# Ethernet_Connector.net
KiCad netlist of a schematic drawn in Altium Designer
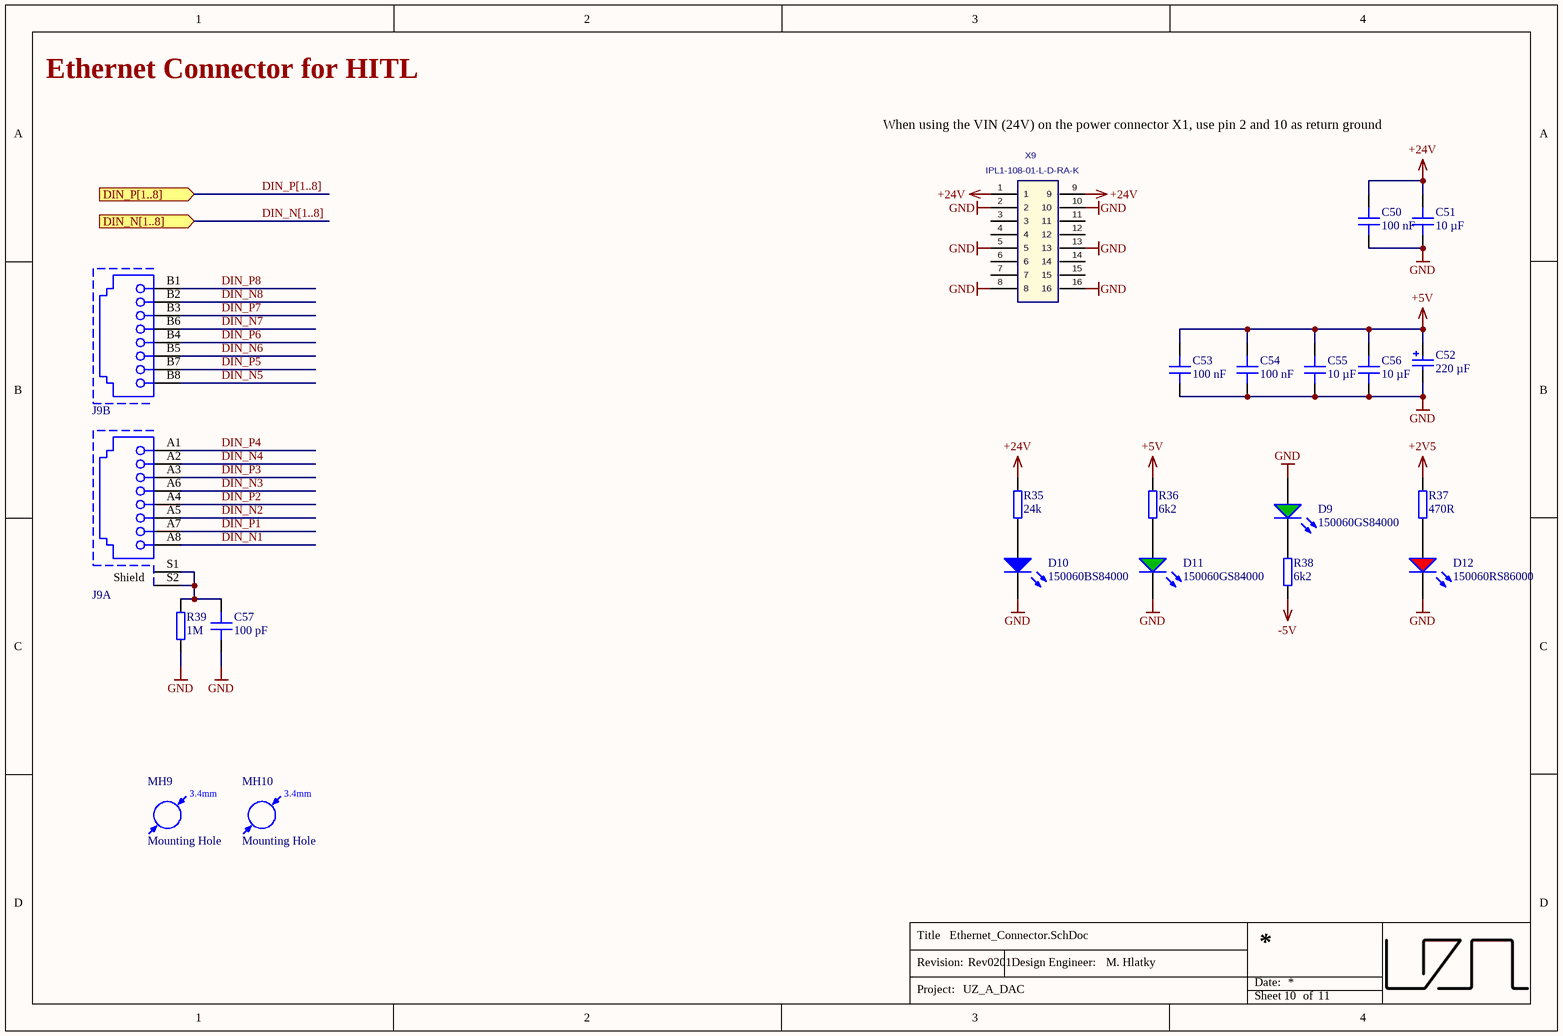
[diagram p0: Ethernet_Connector.SchDoc]

(export (version "E")
  (design (tool "Eeschema 10.0.6"))
  (components
    (comp (ref "C50")
      (value "100 nF")
      (footprint "C_0603")
      (description "Capacitor 0603, 6.3 VDC, 100 nF, X5R")
      (fields
        (field (name "MANUFACTURER PART NUMBER") "C0603C104K9PACTU")
        (field (name "MANUFACTURER") "KEMET")
        (field (name "CREATED FROM") "MGremer")
      )
      (libsource (lib "user") (part "Capacitor"))
    )
    (comp (ref "C51")
      (value "10 µF")
      (footprint "C_1206")
      (description "Capacitor 1206, 50 VDC, 10 µF, X5R")
      (fields
        (field (name "MANUFACTURER PART NUMBER") "GRT31CR61H106KE01L")
        (field (name "MANUFACTURER") "Murata Electronics")
        (field (name "CREATED FROM") "MGremer")
      )
      (libsource (lib "user") (part "Capacitor"))
    )
    (comp (ref "C52")
      (value "220 µF")
      (footprint "WCAP-PSHP_D8mm x L7.7mm")
      (description "Capacitor WCAP, 16 VDC, 220 µF")
      (fields
        (field (name "MANUFACTURER PART NUMBER") "875115350002")
        (field (name "MANUFACTURER") "Wuerth Elektronik")
        (field (name "CREATED FROM") "MGremer")
      )
      (libsource (lib "user") (part "Capacitor_Polarized"))
    )
    (comp (ref "C53")
      (value "100 nF")
      (footprint "C_0603")
      (description "Capacitor 0603, 6.3 VDC, 100 nF, X5R")
      (fields
        (field (name "MANUFACTURER PART NUMBER") "C0603C104K9PACTU")
        (field (name "MANUFACTURER") "KEMET")
        (field (name "CREATED FROM") "MGremer")
      )
      (libsource (lib "user") (part "Capacitor"))
    )
    (comp (ref "C54")
      (value "100 nF")
      (footprint "C_0603")
      (description "Capacitor 0603, 6.3 VDC, 100 nF, X5R")
      (fields
        (field (name "MANUFACTURER PART NUMBER") "C0603C104K9PACTU")
        (field (name "MANUFACTURER") "KEMET")
        (field (name "CREATED FROM") "MGremer")
      )
      (libsource (lib "user") (part "Capacitor"))
    )
    (comp (ref "C55")
      (value "10 µF")
      (footprint "C_1206")
      (description "Capacitor 1206, 50 VDC, 10 µF, X5R")
      (fields
        (field (name "MANUFACTURER PART NUMBER") "GRT31CR61H106KE01L")
        (field (name "MANUFACTURER") "Murata Electronics")
        (field (name "CREATED FROM") "MGremer")
      )
      (libsource (lib "user") (part "Capacitor"))
    )
    (comp (ref "C56")
      (value "10 µF")
      (footprint "C_1206")
      (description "Capacitor 1206, 50 VDC, 10 µF, X5R")
      (fields
        (field (name "MANUFACTURER PART NUMBER") "GRT31CR61H106KE01L")
        (field (name "MANUFACTURER") "Murata Electronics")
        (field (name "CREATED FROM") "MGremer")
      )
      (libsource (lib "user") (part "Capacitor"))
    )
    (comp (ref "C57")
      (value "100 pF")
      (footprint "C_1206")
      (description "Capacitor 1206, 1 kVDC, 100 pF, C0G")
      (fields
        (field (name "MANUFACTURER PART NUMBER") "885342008009")
        (field (name "MANUFACTURER") "Wuerth Elektronik")
        (field (name "CREATED FROM") "MGremer")
      )
      (libsource (lib "user") (part "Capacitor"))
    )
    (comp (ref "D9")
      (value "150060GS84000")
      (footprint "WL-SMCW_0603")
      (description "WL-SMCW SMD Mono-color Chip LED Waterclear Green")
      (fields (field (name "MANUFACTURER") "Wuerth Elektronik") (field (name "CREATED FROM") "MGremer"))
      (libsource (lib "user") (part "LED_Green"))
    )
    (comp (ref "D10")
      (value "150060BS84000")
      (footprint "WL-SMCW_0603")
      (description "WL-SMCW SMD Mono-color Chip LED Waterclear Blue")
      (fields (field (name "MANUFACTURER") "Wuerth Elektronik") (field (name "CREATED FROM") "MGremer"))
      (libsource (lib "user") (part "LED_Blue"))
    )
    (comp (ref "D11")
      (value "150060GS84000")
      (footprint "WL-SMCW_0603")
      (description "WL-SMCW SMD Mono-color Chip LED Waterclear Green")
      (fields (field (name "MANUFACTURER") "Wuerth Elektronik") (field (name "CREATED FROM") "MGremer"))
      (libsource (lib "user") (part "LED_Green"))
    )
    (comp (ref "D12")
      (value "150060RS86000")
      (footprint "WL-SMCW_0603")
      (description "WL-SMCW SMD Mono-color Chip LED Waterclear Red")
      (fields (field (name "MANUFACTURER") "Wuerth Elektronik") (field (name "CREATED FROM") "MGremer"))
      (libsource (lib "user") (part "LED_Red"))
    )
    (comp (ref "J9")
      (value "RJHSE-5380-02")
      (footprint "RJHSE-5380-02")
      (description "TAB-UP, MULTIPORT, RIGHT ANGLE OR VERTICAL WITH SHIELD AND INTEGRATED LEDs")
      (fields (field (name "MF") "Amphenol") (field (name "CREATED FROM") "MHlatky"))
      (libsource (lib "user") (part "RJHSE-5380-02"))
    )
    (comp (ref "MH9")
      (value "Mounting Hole")
      (footprint "MH_3.4")
      (fields (field (name "CREATED FROM") "MHlatky"))
      (libsource (lib "user") (part "Mounting Hole"))
    )
    (comp (ref "MH10")
      (value "Mounting Hole")
      (footprint "MH_3.4")
      (fields (field (name "CREATED FROM") "MHlatky"))
      (libsource (lib "user") (part "Mounting Hole"))
    )
    (comp (ref "R35")
      (value "24k")
      (footprint "RES 0603_1608")
      (description "SMD resistor E24 series")
      (fields
        (field (name "MANUFACTURER PART NUMBER") "RK73B1JTTD243J")
        (field (name "MANUFACTURER") "KOA Speer")
        (field (name "CREATED FROM") "MGremer")
      )
      (libsource (lib "user") (part "Resistor"))
    )
    (comp (ref "R36")
      (value "6k2")
      (footprint "RES 0603_1608")
      (description "SMD resistor E24 series")
      (fields
        (field (name "MANUFACTURER PART NUMBER") "RK73B1JTTD622J")
        (field (name "MANUFACTURER") "KOA Speer")
        (field (name "CREATED FROM") "MGremer")
      )
      (libsource (lib "user") (part "Resistor"))
    )
    (comp (ref "R37")
      (value "470R")
      (footprint "RES 0603_1608")
      (description "SMD resistor E24 series")
      (fields
        (field (name "MANUFACTURER PART NUMBER") "RK73B1JTTD471J")
        (field (name "MANUFACTURER") "KOA Speer")
        (field (name "CREATED FROM") "MGremer")
      )
      (libsource (lib "user") (part "Resistor"))
    )
    (comp (ref "R38")
      (value "6k2")
      (footprint "RES 0603_1608")
      (description "SMD resistor E24 series")
      (fields
        (field (name "MANUFACTURER PART NUMBER") "RK73B1JTTD622J")
        (field (name "MANUFACTURER") "KOA Speer")
        (field (name "CREATED FROM") "MGremer")
      )
      (libsource (lib "user") (part "Resistor"))
    )
    (comp (ref "R39")
      (value "1M")
      (footprint "RES 0603_1608")
      (description "SMD resistor 1%")
      (fields
        (field (name "MANUFACTURER PART NUMBER") "CRCW06031M00FKEAC")
        (field (name "MANUFACTURER") "Vishay / Dale")
        (field (name "CREATED FROM") "MGremer")
      )
      (libsource (lib "user") (part "Resistor"))
    )
    (comp (ref "X9")
      (value "IPL1-108-01-L-D-RA-K")
      (footprint "IPL1-108-01-L-D-RA-K")
      (description "2.54 mm Double Row Termin Assembly (right angle)")
      (fields (field (name "MANUFACTURER") "SAMTEC") (field (name "CREATED FROM") "MGremer"))
      (libsource (lib "user") (part "IPL1-108-XX-X-D-X"))
    )
  )
  (nets
    (net (code "1") (name "+2V5") (class "Default")
      (node (ref "R37") (pin "2") (pinfunction "2_2") (pintype "passive"))
    )
    (net (code "2") (name "+5V") (class "Default")
      (node (ref "C52") (pin "1") (pinfunction "P_1") (pintype "passive"))
      (node (ref "C53") (pin "2") (pinfunction "2_2") (pintype "passive"))
      (node (ref "C54") (pin "2") (pinfunction "2_2") (pintype "passive"))
      (node (ref "C55") (pin "2") (pinfunction "2_2") (pintype "passive"))
      (node (ref "C56") (pin "2") (pinfunction "2_2") (pintype "passive"))
      (node (ref "R36") (pin "2") (pinfunction "2_2") (pintype "passive"))
    )
    (net (code "3") (name "+24V") (class "Default")
      (node (ref "C50") (pin "2") (pinfunction "2_2") (pintype "passive"))
      (node (ref "C51") (pin "2") (pinfunction "2_2") (pintype "passive"))
      (node (ref "R35") (pin "2") (pinfunction "2_2") (pintype "passive"))
      (node (ref "X9") (pin "1") (pinfunction "1_1") (pintype "passive"))
      (node (ref "X9") (pin "9") (pinfunction "9_9") (pintype "passive"))
    )
    (net (code "4") (name "-5V") (class "Default")
      (node (ref "R38") (pin "1") (pinfunction "1_1") (pintype "passive"))
    )
    (net (code "5") (name "/DIN_N1") (class "Default")
      (node (ref "J9") (pin "A8") (pinfunction "A8_A8") (pintype "passive"))
    )
    (net (code "6") (name "/DIN_N2") (class "Default")
      (node (ref "J9") (pin "A5") (pinfunction "A5_A5") (pintype "passive"))
    )
    (net (code "7") (name "/DIN_N3") (class "Default")
      (node (ref "J9") (pin "A6") (pinfunction "A6_A6") (pintype "passive"))
    )
    (net (code "8") (name "/DIN_N4") (class "Default")
      (node (ref "J9") (pin "A2") (pinfunction "A2_A2") (pintype "passive"))
    )
    (net (code "9") (name "/DIN_N5") (class "Default")
      (node (ref "J9") (pin "B8") (pinfunction "B8_B8") (pintype "passive"))
    )
    (net (code "10") (name "/DIN_N6") (class "Default")
      (node (ref "J9") (pin "B5") (pinfunction "B5_B5") (pintype "passive"))
    )
    (net (code "11") (name "/DIN_N7") (class "Default")
      (node (ref "J9") (pin "B6") (pinfunction "B6_B6") (pintype "passive"))
    )
    (net (code "12") (name "/DIN_N8") (class "Default")
      (node (ref "J9") (pin "B2") (pinfunction "B2_B2") (pintype "passive"))
    )
    (net (code "14") (name "/DIN_P1") (class "Default")
      (node (ref "J9") (pin "A7") (pinfunction "A7_A7") (pintype "passive"))
    )
    (net (code "15") (name "/DIN_P2") (class "Default")
      (node (ref "J9") (pin "A4") (pinfunction "A4_A4") (pintype "passive"))
    )
    (net (code "16") (name "/DIN_P3") (class "Default")
      (node (ref "J9") (pin "A3") (pinfunction "A3_A3") (pintype "passive"))
    )
    (net (code "17") (name "/DIN_P4") (class "Default")
      (node (ref "J9") (pin "A1") (pinfunction "A1_A1") (pintype "passive"))
    )
    (net (code "18") (name "/DIN_P5") (class "Default")
      (node (ref "J9") (pin "B7") (pinfunction "B7_B7") (pintype "passive"))
    )
    (net (code "19") (name "/DIN_P6") (class "Default")
      (node (ref "J9") (pin "B4") (pinfunction "B4_B4") (pintype "passive"))
    )
    (net (code "20") (name "/DIN_P7") (class "Default")
      (node (ref "J9") (pin "B3") (pinfunction "B3_B3") (pintype "passive"))
    )
    (net (code "21") (name "/DIN_P8") (class "Default")
      (node (ref "J9") (pin "B1") (pinfunction "B1_B1") (pintype "passive"))
    )
    (net (code "23") (name "GND") (class "Default")
      (node (ref "C50") (pin "1") (pinfunction "1_1") (pintype "passive"))
      (node (ref "C51") (pin "1") (pinfunction "1_1") (pintype "passive"))
      (node (ref "C52") (pin "2") (pinfunction "N_2") (pintype "passive"))
      (node (ref "C53") (pin "1") (pinfunction "1_1") (pintype "passive"))
      (node (ref "C54") (pin "1") (pinfunction "1_1") (pintype "passive"))
      (node (ref "C55") (pin "1") (pinfunction "1_1") (pintype "passive"))
      (node (ref "C56") (pin "1") (pinfunction "1_1") (pintype "passive"))
      (node (ref "C57") (pin "1") (pinfunction "1_1") (pintype "passive"))
      (node (ref "D10") (pin "1") (pinfunction "K_1") (pintype "passive"))
      (node (ref "D11") (pin "1") (pinfunction "K_1") (pintype "passive"))
      (node (ref "D12") (pin "1") (pinfunction "K_1") (pintype "passive"))
      (node (ref "D9") (pin "2") (pinfunction "A_2") (pintype "passive"))
      (node (ref "R39") (pin "1") (pinfunction "1_1") (pintype "passive"))
      (node (ref "X9") (pin "10") (pinfunction "10_10") (pintype "passive"))
      (node (ref "X9") (pin "13") (pinfunction "13_13") (pintype "passive"))
      (node (ref "X9") (pin "16") (pinfunction "16_16") (pintype "passive"))
      (node (ref "X9") (pin "2") (pinfunction "2_2") (pintype "passive"))
      (node (ref "X9") (pin "5") (pinfunction "5_5") (pintype "passive"))
      (node (ref "X9") (pin "8") (pinfunction "8_8") (pintype "passive"))
    )
    (net (code "24") (name "Net-(C57-Pad2)") (class "Default")
      (node (ref "C57") (pin "2") (pinfunction "2_2") (pintype "passive"))
      (node (ref "J9") (pin "S1") (pinfunction "S1_S1") (pintype "passive"))
      (node (ref "J9") (pin "S2") (pinfunction "S2_S2") (pintype "passive"))
      (node (ref "R39") (pin "2") (pinfunction "2_2") (pintype "passive"))
    )
    (net (code "25") (name "Net-(D9-K)") (class "Default")
      (node (ref "D9") (pin "1") (pinfunction "K_1") (pintype "passive"))
      (node (ref "R38") (pin "2") (pinfunction "2_2") (pintype "passive"))
    )
    (net (code "26") (name "Net-(D10-A)") (class "Default")
      (node (ref "D10") (pin "2") (pinfunction "A_2") (pintype "passive"))
      (node (ref "R35") (pin "1") (pinfunction "1_1") (pintype "passive"))
    )
    (net (code "27") (name "Net-(D11-A)") (class "Default")
      (node (ref "D11") (pin "2") (pinfunction "A_2") (pintype "passive"))
      (node (ref "R36") (pin "1") (pinfunction "1_1") (pintype "passive"))
    )
    (net (code "28") (name "Net-(D12-A)") (class "Default")
      (node (ref "D12") (pin "2") (pinfunction "A_2") (pintype "passive"))
      (node (ref "R37") (pin "1") (pinfunction "1_1") (pintype "passive"))
    )
    (net (code "29") (name "unconnected-(X9-Pad3)") (class "Default")
      (node (ref "X9") (pin "3") (pinfunction "3_3") (pintype "passive"))
    )
    (net (code "30") (name "unconnected-(X9-Pad4)") (class "Default")
      (node (ref "X9") (pin "4") (pinfunction "4_4") (pintype "passive"))
    )
    (net (code "31") (name "unconnected-(X9-Pad6)") (class "Default")
      (node (ref "X9") (pin "6") (pinfunction "6_6") (pintype "passive"))
    )
    (net (code "32") (name "unconnected-(X9-Pad7)") (class "Default")
      (node (ref "X9") (pin "7") (pinfunction "7_7") (pintype "passive"))
    )
    (net (code "33") (name "unconnected-(X9-Pad11)") (class "Default")
      (node (ref "X9") (pin "11") (pinfunction "11_11") (pintype "passive"))
    )
    (net (code "34") (name "unconnected-(X9-Pad12)") (class "Default")
      (node (ref "X9") (pin "12") (pinfunction "12_12") (pintype "passive"))
    )
    (net (code "35") (name "unconnected-(X9-Pad14)") (class "Default")
      (node (ref "X9") (pin "14") (pinfunction "14_14") (pintype "passive"))
    )
    (net (code "36") (name "unconnected-(X9-Pad15)") (class "Default")
      (node (ref "X9") (pin "15") (pinfunction "15_15") (pintype "passive"))
    )
  )
)
